# SensorBoard.net
KiCad netlist of a schematic drawn in EAGLE
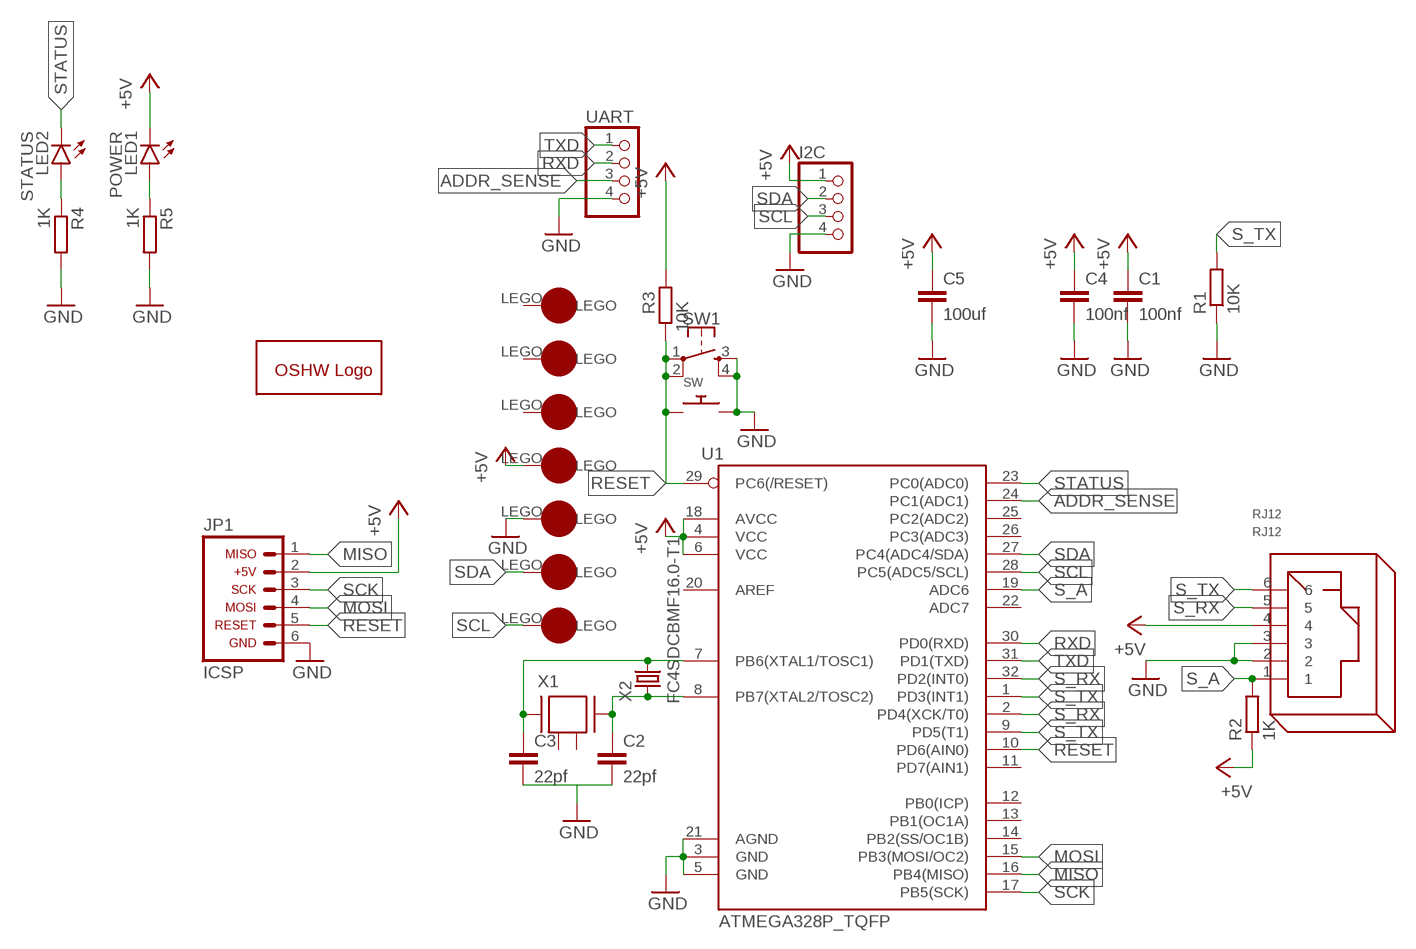
[diagram p0: schematic, sheet 1]

(export (version "E")
  (design (tool "Eeschema 10.0.6"))
  (components
    (comp (ref "C1")
      (value "100nf")
      (footprint "eagle-import:C1206")
      (libsource (lib "eagle-import") (part "C-EUC1206"))
    )
    (comp (ref "C2")
      (value "22pf")
      (footprint "eagle-import:C1206")
      (libsource (lib "eagle-import") (part "C-EUC1206"))
    )
    (comp (ref "C3")
      (value "22pf")
      (footprint "eagle-import:C1206")
      (libsource (lib "eagle-import") (part "C-EUC1206"))
    )
    (comp (ref "C4")
      (value "100nf")
      (footprint "eagle-import:C1206")
      (libsource (lib "eagle-import") (part "C-EUC1206"))
    )
    (comp (ref "C5")
      (value "100uf")
      (footprint "eagle-import:C1206")
      (libsource (lib "eagle-import") (part "C-EUC1206"))
    )
    (comp (ref "I2C")
      (value "PINHD-1X4")
      (footprint "eagle-import:1X04")
      (libsource (lib "eagle-import") (part "PINHD-1X4"))
    )
    (comp (ref "JP1")
      (value "ICSP_HEADER")
      (footprint "eagle-import:ICSP_HEADER")
      (libsource (lib "eagle-import") (part "ICSP_HEADER"))
    )
    (comp (ref "LED1")
      (value "POWER")
      (footprint "eagle-import:1206")
      (libsource (lib "eagle-import") (part "LEDSMT1206"))
    )
    (comp (ref "LED2")
      (value "STATUS")
      (footprint "eagle-import:1206")
      (libsource (lib "eagle-import") (part "LEDSMT1206"))
    )
    (comp (ref "R1")
      (value "10K")
      (footprint "eagle-import:M1206")
      (libsource (lib "eagle-import") (part "R-EU_M1206"))
    )
    (comp (ref "R2")
      (value "1K")
      (footprint "eagle-import:M1206")
      (libsource (lib "eagle-import") (part "R-EU_M1206"))
    )
    (comp (ref "R3")
      (value "10K")
      (footprint "eagle-import:M1206")
      (libsource (lib "eagle-import") (part "R-EU_M1206"))
    )
    (comp (ref "R4")
      (value "1K")
      (footprint "eagle-import:M1206")
      (libsource (lib "eagle-import") (part "R-EU_M1206"))
    )
    (comp (ref "R5")
      (value "1K")
      (footprint "eagle-import:M1206")
      (libsource (lib "eagle-import") (part "R-EU_M1206"))
    )
    (comp (ref "RJ12")
      (value "RJ12")
      (footprint "eagle-import:RJ12")
      (libsource (lib "eagle-import") (part "RJ12"))
    )
    (comp (ref "SW")
      (value "SWITCH_PUSHBUTTONC&K_KSS")
      (footprint "eagle-import:BTN_CK_KSS")
      (libsource (lib "eagle-import") (part "SWITCH_PUSHBUTTONC&K_KSS"))
    )
    (comp (ref "SW1")
      (value "MOMENTARY-SWITCH-SPST-2-SMD-5.2MM")
      (footprint "eagle-import:TACTILE_SWITCH_SMD_5.2MM")
      (libsource (lib "eagle-import") (part "MOMENTARY-SWITCH-SPST-2-SMD-5.2MM"))
    )
    (comp (ref "U$1")
      (value "LEGO-1X1")
      (footprint "eagle-import:LEGO-1X1")
      (libsource (lib "eagle-import") (part "LEGO-1X1"))
    )
    (comp (ref "U$2")
      (value "OPENSOURCE")
      (footprint "eagle-import:OSHW_5MM")
      (libsource (lib "eagle-import") (part "OPENSOURCE"))
    )
    (comp (ref "U$3")
      (value "LEGO-1X1")
      (footprint "eagle-import:LEGO-1X1")
      (libsource (lib "eagle-import") (part "LEGO-1X1"))
    )
    (comp (ref "U$4")
      (value "LEGO-1X1")
      (footprint "eagle-import:LEGO-1X1")
      (libsource (lib "eagle-import") (part "LEGO-1X1"))
    )
    (comp (ref "U$5")
      (value "LEGO-1X1")
      (footprint "eagle-import:LEGO-1X1")
      (libsource (lib "eagle-import") (part "LEGO-1X1"))
    )
    (comp (ref "U$6")
      (value "LEGO-1X1")
      (footprint "eagle-import:LEGO-1X1")
      (libsource (lib "eagle-import") (part "LEGO-1X1"))
    )
    (comp (ref "U$7")
      (value "LEGO-1X1")
      (footprint "eagle-import:LEGO-1X1")
      (libsource (lib "eagle-import") (part "LEGO-1X1"))
    )
    (comp (ref "U$9")
      (value "LEGO-1X1")
      (footprint "eagle-import:LEGO-1X1")
      (libsource (lib "eagle-import") (part "LEGO-1X1"))
    )
    (comp (ref "U1")
      (value "ATMEGA328P_TQFP")
      (footprint "eagle-import:TQFP32-08")
      (libsource (lib "eagle-import") (part "ATMEGA328P_TQFP"))
    )
    (comp (ref "UART")
      (value "PINHD-1X4")
      (footprint "eagle-import:1X04")
      (libsource (lib "eagle-import") (part "PINHD-1X4"))
    )
    (comp (ref "X1")
      (value "7B-16.000MAAJ-T")
      (footprint "eagle-import:7B-16.000MAAJ-T")
      (fields
        (field (name "DIGIKEY_PART_NUMBER") "887-1104-2-ND")
        (field (name "MANUFACTURER") "TXC CORPORATION")
      )
      (libsource (lib "eagle-import") (part "7B-16.000MAAJ-T"))
    )
    (comp (ref "X2")
      (value "FC4SDCBMF16.0-T1")
      (footprint "eagle-import:FC4SDCBMF16.0-T1")
      (fields
        (field (name "DIGIKEY_PART_NUMBER") "631-1017-2-ND")
        (field (name "MANUFACTURER") "Fox Electronics")
        (field (name "CREATED_BY") "PCBLayout.com")
      )
      (libsource (lib "eagle-import") (part "FC4SDCBMF16.0-T1"))
    )
  )
  (nets
    (net (code "1") (name "+5V") (class "Default")
      (node (ref "C1") (pin "1") (pinfunction "1_1") (pintype "passive"))
      (node (ref "C4") (pin "1") (pinfunction "1_1") (pintype "passive"))
      (node (ref "C5") (pin "1") (pinfunction "1_1") (pintype "passive"))
      (node (ref "I2C") (pin "1") (pinfunction "1_1") (pintype "passive"))
      (node (ref "JP1") (pin "2") (pinfunction "2_2") (pintype "passive"))
      (node (ref "LED1") (pin "C") (pinfunction "C_C") (pintype "passive"))
      (node (ref "R2") (pin "1") (pinfunction "1_1") (pintype "passive"))
      (node (ref "R3") (pin "2") (pinfunction "2_2") (pintype "passive"))
      (node (ref "RJ12") (pin "4") (pinfunction "4_4") (pintype "bidirectional"))
      (node (ref "U$5") (pin "LEGO") (pinfunction "LEGO_LEGO") (pintype "bidirectional"))
      (node (ref "U1") (pin "18") (pinfunction "AVCC_18") (pintype "bidirectional"))
      (node (ref "U1") (pin "4") (pinfunction "VCC_4") (pintype "bidirectional"))
      (node (ref "U1") (pin "6") (pinfunction "VCC_6") (pintype "bidirectional"))
    )
    (net (code "2") (name "ADDR_SENSE") (class "Default")
      (node (ref "U1") (pin "24") (pinfunction "PC1(ADC1)_24") (pintype "bidirectional"))
      (node (ref "UART") (pin "3") (pinfunction "3_3") (pintype "passive"))
    )
    (net (code "3") (name "GND") (class "Default")
      (node (ref "C1") (pin "2") (pinfunction "2_2") (pintype "passive"))
      (node (ref "C2") (pin "2") (pinfunction "2_2") (pintype "passive"))
      (node (ref "C3") (pin "2") (pinfunction "2_2") (pintype "passive"))
      (node (ref "C4") (pin "2") (pinfunction "2_2") (pintype "passive"))
      (node (ref "C5") (pin "2") (pinfunction "2_2") (pintype "passive"))
      (node (ref "I2C") (pin "4") (pinfunction "4_4") (pintype "passive"))
      (node (ref "JP1") (pin "6") (pinfunction "6_6") (pintype "passive"))
      (node (ref "R1") (pin "1") (pinfunction "1_1") (pintype "passive"))
      (node (ref "R4") (pin "2") (pinfunction "2_2") (pintype "passive"))
      (node (ref "R5") (pin "2") (pinfunction "2_2") (pintype "passive"))
      (node (ref "RJ12") (pin "2") (pinfunction "2_2") (pintype "bidirectional"))
      (node (ref "RJ12") (pin "3") (pinfunction "3_3") (pintype "bidirectional"))
      (node (ref "SW") (pin "P$2") (pinfunction "P$2_P$2") (pintype "passive"))
      (node (ref "SW1") (pin "3") (pinfunction "3_3") (pintype "passive"))
      (node (ref "SW1") (pin "4") (pinfunction "4_4") (pintype "passive"))
      (node (ref "U$4") (pin "LEGO") (pinfunction "LEGO_LEGO") (pintype "bidirectional"))
      (node (ref "U1") (pin "21") (pinfunction "AGND_21") (pintype "bidirectional"))
      (node (ref "U1") (pin "3") (pinfunction "GND_3") (pintype "bidirectional"))
      (node (ref "U1") (pin "5") (pinfunction "GND_5") (pintype "bidirectional"))
      (node (ref "UART") (pin "4") (pinfunction "4_4") (pintype "passive"))
    )
    (net (code "4") (name "MISO") (class "Default")
      (node (ref "JP1") (pin "1") (pinfunction "1_1") (pintype "passive"))
      (node (ref "U1") (pin "16") (pinfunction "PB4(MISO)_16") (pintype "bidirectional"))
    )
    (net (code "5") (name "MOSI") (class "Default")
      (node (ref "JP1") (pin "4") (pinfunction "4_4") (pintype "passive"))
      (node (ref "U1") (pin "15") (pinfunction "PB3(MOSI/OC2)_15") (pintype "bidirectional"))
    )
    (net (code "6") (name "Net-(LED1-PadA)") (class "Default")
      (node (ref "LED1") (pin "A") (pinfunction "A_A") (pintype "passive"))
      (node (ref "R5") (pin "1") (pinfunction "1_1") (pintype "passive"))
    )
    (net (code "7") (name "Net-(LED2-PadA)") (class "Default")
      (node (ref "LED2") (pin "A") (pinfunction "A_A") (pintype "passive"))
      (node (ref "R4") (pin "1") (pinfunction "1_1") (pintype "passive"))
    )
    (net (code "8") (name "Net-(U1-PB6(XTAL1{slash}TOSC1))") (class "Default")
      (node (ref "C3") (pin "1") (pinfunction "1_1") (pintype "passive"))
      (node (ref "U1") (pin "7") (pinfunction "PB6(XTAL1/TOSC1)_7") (pintype "bidirectional"))
      (node (ref "X1") (pin "1") (pinfunction "1_1") (pintype "passive"))
      (node (ref "X2") (pin "2") (pinfunction "2_2") (pintype "passive"))
    )
    (net (code "9") (name "Net-(U1-PB7(XTAL2{slash}TOSC2))") (class "Default")
      (node (ref "C2") (pin "1") (pinfunction "1_1") (pintype "passive"))
      (node (ref "U1") (pin "8") (pinfunction "PB7(XTAL2/TOSC2)_8") (pintype "bidirectional"))
      (node (ref "X1") (pin "3") (pinfunction "3_3") (pintype "passive"))
      (node (ref "X2") (pin "1") (pinfunction "1_1") (pintype "passive"))
    )
    (net (code "10") (name "RESET") (class "Default")
      (node (ref "JP1") (pin "5") (pinfunction "5_5") (pintype "passive"))
      (node (ref "R3") (pin "1") (pinfunction "1_1") (pintype "passive"))
      (node (ref "SW") (pin "P$1") (pinfunction "P$1_P$1") (pintype "passive"))
      (node (ref "SW1") (pin "1") (pinfunction "1_1") (pintype "passive"))
      (node (ref "SW1") (pin "2") (pinfunction "2_2") (pintype "passive"))
      (node (ref "U1") (pin "10") (pinfunction "PD6(AIN0)_10") (pintype "bidirectional"))
      (node (ref "U1") (pin "29") (pinfunction "PC6(/RESET)_29") (pintype "bidirectional"))
    )
    (net (code "11") (name "RXD") (class "Default")
      (node (ref "U1") (pin "30") (pinfunction "PD0(RXD)_30") (pintype "bidirectional"))
      (node (ref "UART") (pin "2") (pinfunction "2_2") (pintype "passive"))
    )
    (net (code "12") (name "SCK") (class "Default")
      (node (ref "JP1") (pin "3") (pinfunction "3_3") (pintype "passive"))
      (node (ref "U1") (pin "17") (pinfunction "PB5(SCK)_17") (pintype "bidirectional"))
    )
    (net (code "13") (name "SCL") (class "Default")
      (node (ref "I2C") (pin "3") (pinfunction "3_3") (pintype "passive"))
      (node (ref "U$1") (pin "LEGO") (pinfunction "LEGO_LEGO") (pintype "bidirectional"))
      (node (ref "U1") (pin "28") (pinfunction "PC5(ADC5/SCL)_28") (pintype "bidirectional"))
    )
    (net (code "14") (name "SDA") (class "Default")
      (node (ref "I2C") (pin "2") (pinfunction "2_2") (pintype "passive"))
      (node (ref "U$3") (pin "LEGO") (pinfunction "LEGO_LEGO") (pintype "bidirectional"))
      (node (ref "U1") (pin "27") (pinfunction "PC4(ADC4/SDA)_27") (pintype "bidirectional"))
    )
    (net (code "15") (name "STATUS") (class "Default")
      (node (ref "LED2") (pin "C") (pinfunction "C_C") (pintype "passive"))
      (node (ref "U1") (pin "23") (pinfunction "PC0(ADC0)_23") (pintype "bidirectional"))
    )
    (net (code "16") (name "S_A") (class "Default")
      (node (ref "R2") (pin "2") (pinfunction "2_2") (pintype "passive"))
      (node (ref "RJ12") (pin "1") (pinfunction "1_1") (pintype "bidirectional"))
      (node (ref "U1") (pin "19") (pinfunction "ADC6_19") (pintype "bidirectional"))
    )
    (net (code "17") (name "S_RX") (class "Default")
      (node (ref "RJ12") (pin "5") (pinfunction "5_5") (pintype "bidirectional"))
      (node (ref "U1") (pin "2") (pinfunction "PD4(XCK/T0)_2") (pintype "bidirectional"))
      (node (ref "U1") (pin "32") (pinfunction "PD2(INT0)_32") (pintype "bidirectional"))
    )
    (net (code "18") (name "S_TX") (class "Default")
      (node (ref "R1") (pin "2") (pinfunction "2_2") (pintype "passive"))
      (node (ref "RJ12") (pin "6") (pinfunction "6_6") (pintype "bidirectional"))
      (node (ref "U1") (pin "1") (pinfunction "PD3(INT1)_1") (pintype "bidirectional"))
      (node (ref "U1") (pin "9") (pinfunction "PD5(T1)_9") (pintype "bidirectional"))
    )
    (net (code "19") (name "TXD") (class "Default")
      (node (ref "U1") (pin "31") (pinfunction "PD1(TXD)_31") (pintype "bidirectional"))
      (node (ref "UART") (pin "1") (pinfunction "1_1") (pintype "passive"))
    )
    (net (code "20") (name "unconnected-(U$6-PadLEGO)") (class "Default")
      (node (ref "U$6") (pin "LEGO") (pinfunction "LEGO_LEGO") (pintype "bidirectional"))
    )
    (net (code "21") (name "unconnected-(U$7-PadLEGO)") (class "Default")
      (node (ref "U$7") (pin "LEGO") (pinfunction "LEGO_LEGO") (pintype "bidirectional"))
    )
    (net (code "22") (name "unconnected-(U$9-PadLEGO)") (class "Default")
      (node (ref "U$9") (pin "LEGO") (pinfunction "LEGO_LEGO") (pintype "bidirectional"))
    )
    (net (code "23") (name "unconnected-(U1-ADC7-Pad22)") (class "Default")
      (node (ref "U1") (pin "22") (pinfunction "ADC7_22") (pintype "bidirectional"))
    )
    (net (code "24") (name "unconnected-(U1-AREF-Pad20)") (class "Default")
      (node (ref "U1") (pin "20") (pinfunction "AREF_20") (pintype "bidirectional"))
    )
    (net (code "25") (name "unconnected-(U1-PB0(ICP)-Pad12)") (class "Default")
      (node (ref "U1") (pin "12") (pinfunction "PB0(ICP)_12") (pintype "bidirectional"))
    )
    (net (code "26") (name "unconnected-(U1-PB1(OC1A)-Pad13)") (class "Default")
      (node (ref "U1") (pin "13") (pinfunction "PB1(OC1A)_13") (pintype "bidirectional"))
    )
    (net (code "27") (name "unconnected-(U1-PB2(SS{slash}OC1B)-Pad14)") (class "Default")
      (node (ref "U1") (pin "14") (pinfunction "PB2(SS/OC1B)_14") (pintype "bidirectional"))
    )
    (net (code "28") (name "unconnected-(U1-PC2(ADC2)-Pad25)") (class "Default")
      (node (ref "U1") (pin "25") (pinfunction "PC2(ADC2)_25") (pintype "bidirectional"))
    )
    (net (code "29") (name "unconnected-(U1-PC3(ADC3)-Pad26)") (class "Default")
      (node (ref "U1") (pin "26") (pinfunction "PC3(ADC3)_26") (pintype "bidirectional"))
    )
    (net (code "30") (name "unconnected-(U1-PD7(AIN1)-Pad11)") (class "Default")
      (node (ref "U1") (pin "11") (pinfunction "PD7(AIN1)_11") (pintype "bidirectional"))
    )
    (net (code "31") (name "unconnected-(X1-Pad2)") (class "Default")
      (node (ref "X1") (pin "2") (pinfunction "2_2") (pintype "passive"))
    )
    (net (code "32") (name "unconnected-(X1-Pad4)") (class "Default")
      (node (ref "X1") (pin "4") (pinfunction "4_4") (pintype "passive"))
    )
  )
)
